# TLV2462CP.net
KiCad netlist of a schematic drawn in EAGLE
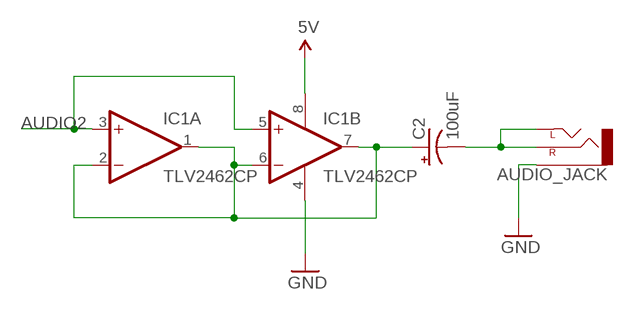
[diagram p0: schematic, sheet 2]

(export (version "E")
  (design (tool "Eeschema 10.0.6"))
  (components
    (comp (ref "AUDIO_JACK")
      (value "AUDIO-JACKPTH")
      (footprint "eagle-import:AUDIO-JACK")
      (libsource (lib "eagle-import") (part "AUDIO-JACKPTH"))
    )
    (comp (ref "C2")
      (value "100uF")
      (footprint "eagle-import:CPOL-RADIAL-100UF-25V")
      (libsource (lib "eagle-import") (part "CAP_POLPTH1"))
    )
    (comp (ref "IC1")
      (value "TLV2462CP")
      (footprint "eagle-import:DIL08")
      (libsource (lib "eagle-import") (part "TL072P"))
    )
  )
  (nets
    (net (code "1") (name "5V") (class "Default")
      (node (ref "IC1") (pin "8") (pinfunction "V+_8") (pintype "power_in"))
    )
    (net (code "2") (name "AUDIO2") (class "Default")
      (node (ref "IC1") (pin "3") (pinfunction "+IN_3") (pintype "input"))
      (node (ref "IC1") (pin "5") (pinfunction "+IN_5") (pintype "input"))
    )
    (net (code "3") (name "GND") (class "Default")
      (node (ref "AUDIO_JACK") (pin "SLEEVE") (pinfunction "SLEEVE_SLEEVE") (pintype "bidirectional"))
      (node (ref "IC1") (pin "4") (pinfunction "V-_4") (pintype "power_in"))
    )
    (net (code "4") (name "Net-(AUDIO_JACK-LEFT)") (class "Default")
      (node (ref "AUDIO_JACK") (pin "RING") (pinfunction "RIGHT_RING") (pintype "bidirectional"))
      (node (ref "AUDIO_JACK") (pin "TIP") (pinfunction "LEFT_TIP") (pintype "bidirectional"))
      (node (ref "C2") (pin "2") (pinfunction "-_2") (pintype "passive"))
    )
    (net (code "5") (name "Net-(C2-+)") (class "Default")
      (node (ref "C2") (pin "1") (pinfunction "+_1") (pintype "passive"))
      (node (ref "IC1") (pin "1") (pinfunction "OUT_1") (pintype "output"))
      (node (ref "IC1") (pin "2") (pinfunction "-IN_2") (pintype "input"))
      (node (ref "IC1") (pin "6") (pinfunction "-IN_6") (pintype "input"))
      (node (ref "IC1") (pin "7") (pinfunction "OUT_7") (pintype "output"))
    )
  )
)
